# KhoaSoDienTu.net
KiCad netlist of a schematic drawn in Altium Designer
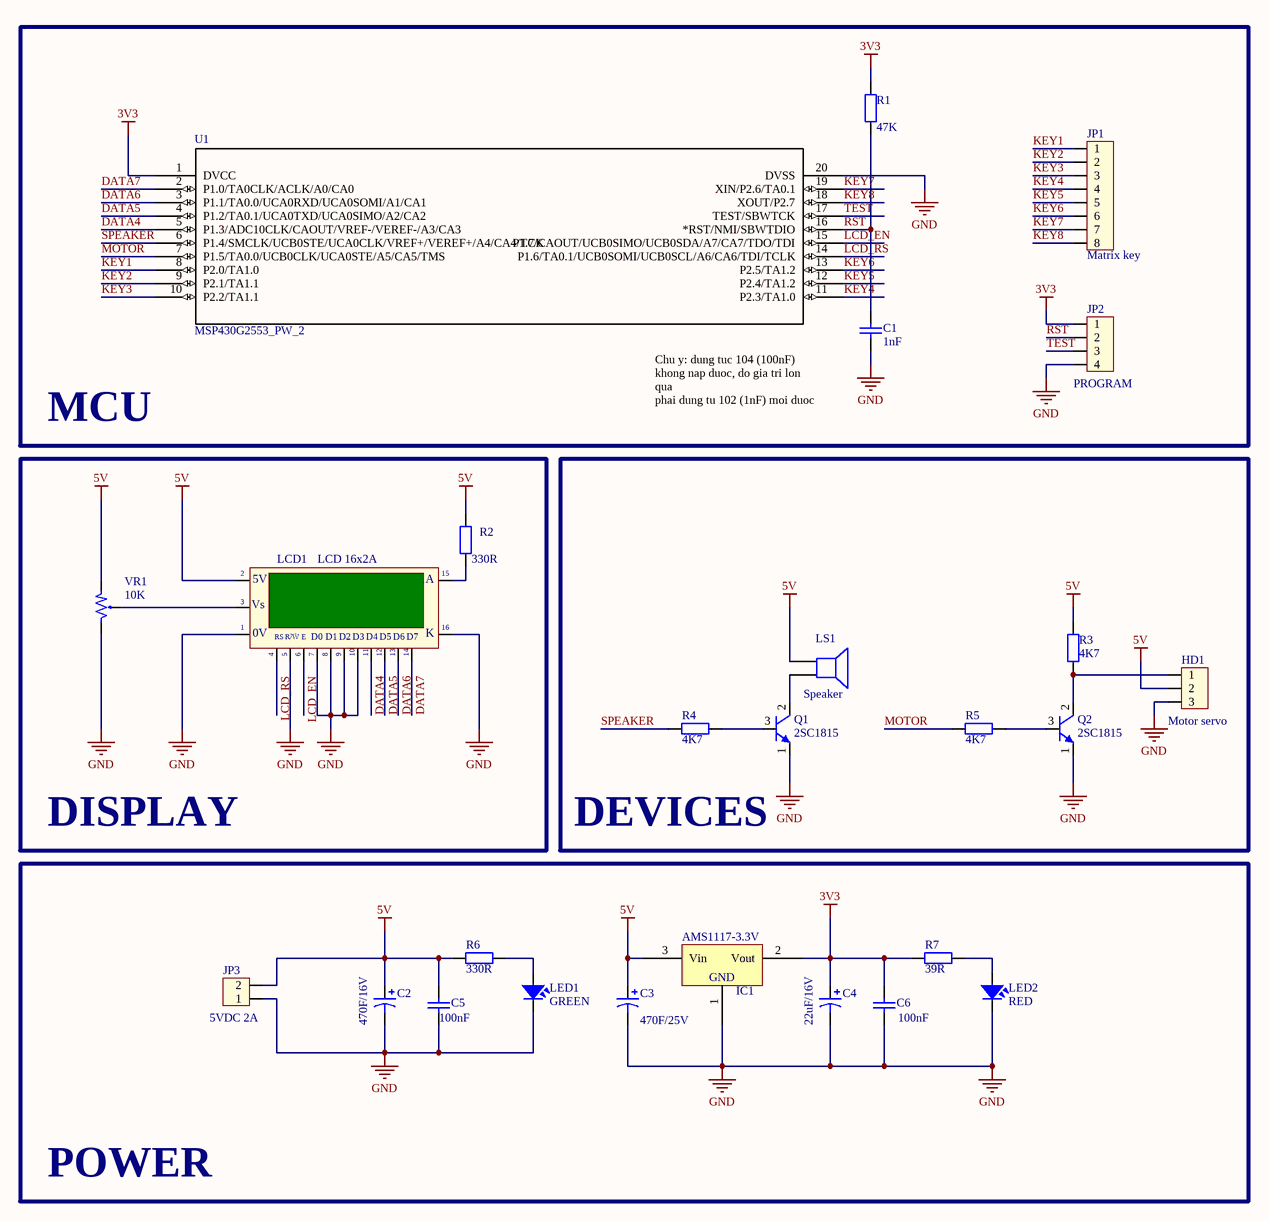
[diagram p0: KhoaSoDienTu.SchDoc]

(export (version "E")
  (design (tool "Eeschema 10.0.6"))
  (components
    (comp (ref "C1")
      (value "1nF")
      (footprint "Tu gom 104")
      (description "Capacitor")
      (fields (field (name "Comment") "Cap") (field (name "PUBLISHER") "Altium Limited"))
      (libsource (lib "Miscellaneous Devices") (part "Cap"))
    )
    (comp (ref "C2")
      (value "470F/16V")
      (footprint "CAP_470UF_16V")
      (description "Polarized Capacitor (Radial)")
      (fields (field (name "Comment") "Cap Pol1") (field (name "PUBLISHER") "Altium Limited"))
      (libsource (lib "Miscellaneous Devices") (part "Cap Pol1"))
    )
    (comp (ref "C3")
      (value "470F/25V")
      (footprint "CAP_470UF_25V")
      (description "Polarized Capacitor (Radial)")
      (fields (field (name "Comment") "Cap Pol1") (field (name "PUBLISHER") "Altium Limited"))
      (libsource (lib "Miscellaneous Devices") (part "Cap Pol1"))
    )
    (comp (ref "C4")
      (value "22uF/16V")
      (footprint "CAP_22UF_16V")
      (description "Polarized Capacitor (Radial)")
      (fields (field (name "Comment") "Cap Pol1") (field (name "PUBLISHER") "Altium Limited"))
      (libsource (lib "Miscellaneous Devices") (part "Cap Pol1"))
    )
    (comp (ref "C5")
      (value "100nF")
      (footprint "Tu gom 104")
      (description "Capacitor")
      (fields (field (name "Comment") "Cap") (field (name "PUBLISHER") "Altium Limited"))
      (libsource (lib "Miscellaneous Devices") (part "Cap"))
    )
    (comp (ref "C6")
      (value "100nF")
      (footprint "Tu gom 104")
      (description "Capacitor")
      (fields (field (name "Comment") "Cap") (field (name "PUBLISHER") "Altium Limited"))
      (libsource (lib "Miscellaneous Devices") (part "Cap"))
    )
    (comp (ref "HD1")
      (value "Motor servo")
      (footprint "Header_3")
      (description "Header 3 (Green)")
      (libsource (lib "lpson") (part "Hed3"))
    )
    (comp (ref "IC1")
      (value "AMS1117-3.3V")
      (footprint "AMS1117-3.3V")
      (libsource (lib "LuanVanPIR") (part "AMS1117"))
    )
    (comp (ref "JP1")
      (value "Matrix key")
      (footprint "Header_8")
      (description "Connector 8")
      (libsource (lib "lpson") (part "Con8"))
    )
    (comp (ref "JP2")
      (value "PROGRAM")
      (footprint "Header_4")
      (description "Connector 4")
      (libsource (lib "lpson") (part "Con4"))
    )
    (comp (ref "JP3")
      (value "5VDC 2A")
      (footprint "CON2")
      (description "Connector 2")
      (libsource (lib "lpson") (part "Con2"))
    )
    (comp (ref "LCD1")
      (value "LCD 16x2A")
      (footprint "LCD16x2")
      (description "LCD dipslay 16 char, 2 line")
      (libsource (lib "VNELEK") (part "LCD16x2A"))
    )
    (comp (ref "LED1")
      (value "GREEN")
      (footprint "LED3G")
      (description "LED Single colour Green and Red")
      (libsource (lib "VNELEK") (part "LED"))
    )
    (comp (ref "LED2")
      (value "RED")
      (footprint "LED3R")
      (description "LED Single colour Green and Red")
      (libsource (lib "VNELEK") (part "LED"))
    )
    (comp (ref "LS1")
      (value "Speaker")
      (footprint "SPEAKER")
      (description "Loudspeaker")
      (fields (field (name "PUBLISHER") "Altium Limited"))
      (libsource (lib "Miscellaneous Devices") (part "Speaker"))
    )
    (comp (ref "Q1")
      (value "2SC1815")
      (footprint "2SC1815")
      (description "Trans NPN 50V 150mA TO-92")
      (libsource (lib "lpson") (part "2SC1815"))
    )
    (comp (ref "Q2")
      (value "2SC1815")
      (footprint "2SC1815")
      (description "Trans NPN 50V 150mA TO-92")
      (libsource (lib "lpson") (part "2SC1815"))
    )
    (comp (ref "R1")
      (value "47K")
      (footprint "RES 1/4W CFR25")
      (description "Resistor")
      (fields (field (name "Comment") "Res2") (field (name "PUBLISHER") "Altium Limited"))
      (libsource (lib "Miscellaneous Devices") (part "Res2"))
    )
    (comp (ref "R2")
      (value "330R")
      (footprint "RES 1/4W CFR25")
      (description "Resistor")
      (fields (field (name "Comment") "Res2") (field (name "PUBLISHER") "Altium Limited"))
      (libsource (lib "Miscellaneous Devices") (part "Res2"))
    )
    (comp (ref "R3")
      (value "4K7")
      (footprint "RES 1/4W CFR25")
      (description "Resistor")
      (fields (field (name "Comment") "Res2") (field (name "PUBLISHER") "Altium Limited"))
      (libsource (lib "Miscellaneous Devices") (part "Res2"))
    )
    (comp (ref "R4")
      (value "4K7")
      (footprint "RES 1/4W CFR25")
      (description "Resistor")
      (fields (field (name "Comment") "Res2") (field (name "PUBLISHER") "Altium Limited"))
      (libsource (lib "") (part "Res2_2"))
    )
    (comp (ref "R5")
      (value "4K7")
      (footprint "RES 1/4W CFR25")
      (description "Resistor")
      (fields (field (name "Comment") "Res2") (field (name "PUBLISHER") "Altium Limited"))
      (libsource (lib "") (part "Res2_2"))
    )
    (comp (ref "R6")
      (value "330R")
      (footprint "RES 1/4W CFR25")
      (description "Resistor")
      (fields (field (name "Comment") "Res2") (field (name "PUBLISHER") "Altium Limited"))
      (libsource (lib "") (part "Res2_1"))
    )
    (comp (ref "R7")
      (value "39R")
      (footprint "RES 1/4W CFR25")
      (description "Resistor")
      (fields (field (name "Comment") "Res2") (field (name "PUBLISHER") "Altium Limited"))
      (libsource (lib "") (part "Res2_1"))
    )
    (comp (ref "U1")
      (value "MSP430G2553_PW_2")
      (footprint "MSP430G2553")
      (description "Imported")
      (fields
        (field (name "MANUFACTURER_PART_NUMBER") "msp430g2553_pw_20")
        (field (name "GENERIC_PART_NUMBER") "MSP430G2553")
      )
      (libsource (lib "MSP430G2553_PW_2") (part "MSP430G2553_PW_2"))
    )
    (comp (ref "VR1")
      (value "10K")
      (footprint "VR1")
      (description "Var Resistor")
      (libsource (lib "VNELEK") (part "VR1"))
    )
  )
  (nets
    (net (code "1") (name "/DATA4") (class "Default")
      (node (ref "LCD1") (pin "11") (pinfunction "D4_11") (pintype "passive"))
      (node (ref "U1") (pin "5") (pinfunction "P1.3/ADC10CLK/CAOUT/VREF-/VEREF-/A3/CA3_5") (pintype "bidirectional"))
    )
    (net (code "2") (name "/DATA5") (class "Default")
      (node (ref "LCD1") (pin "12") (pinfunction "D5_12") (pintype "passive"))
      (node (ref "U1") (pin "4") (pinfunction "P1.2/TA0.1/UCA0TXD/UCA0SIMO/A2/CA2_4") (pintype "bidirectional"))
    )
    (net (code "3") (name "/DATA6") (class "Default")
      (node (ref "LCD1") (pin "13") (pinfunction "D6_13") (pintype "passive"))
      (node (ref "U1") (pin "3") (pinfunction "P1.1/TA0.0/UCA0RXD/UCA0SOMI/A1/CA1_3") (pintype "bidirectional"))
    )
    (net (code "4") (name "/DATA7") (class "Default")
      (node (ref "LCD1") (pin "14") (pinfunction "D7_14") (pintype "passive"))
      (node (ref "U1") (pin "2") (pinfunction "P1.0/TA0CLK/ACLK/A0/CA0_2") (pintype "bidirectional"))
    )
    (net (code "5") (name "/KEY1") (class "Default")
      (node (ref "JP1") (pin "1") (pinfunction "1_1") (pintype "passive"))
      (node (ref "U1") (pin "8") (pinfunction "P2.0/TA1.0_8") (pintype "bidirectional"))
    )
    (net (code "6") (name "/KEY2") (class "Default")
      (node (ref "JP1") (pin "2") (pinfunction "2_2") (pintype "passive"))
      (node (ref "U1") (pin "9") (pinfunction "P2.1/TA1.1_9") (pintype "bidirectional"))
    )
    (net (code "7") (name "/KEY3") (class "Default")
      (node (ref "JP1") (pin "3") (pinfunction "3_3") (pintype "passive"))
      (node (ref "U1") (pin "10") (pinfunction "P2.2/TA1.1_10") (pintype "bidirectional"))
    )
    (net (code "8") (name "/KEY4") (class "Default")
      (node (ref "JP1") (pin "4") (pinfunction "4_4") (pintype "passive"))
      (node (ref "U1") (pin "11") (pinfunction "P2.3/TA1.0_11") (pintype "bidirectional"))
    )
    (net (code "9") (name "/KEY5") (class "Default")
      (node (ref "JP1") (pin "5") (pinfunction "5_5") (pintype "passive"))
      (node (ref "U1") (pin "12") (pinfunction "P2.4/TA1.2_12") (pintype "bidirectional"))
    )
    (net (code "10") (name "/KEY6") (class "Default")
      (node (ref "JP1") (pin "6") (pinfunction "6_6") (pintype "passive"))
      (node (ref "U1") (pin "13") (pinfunction "P2.5/TA1.2_13") (pintype "bidirectional"))
    )
    (net (code "11") (name "/KEY7") (class "Default")
      (node (ref "JP1") (pin "7") (pinfunction "7_7") (pintype "passive"))
      (node (ref "U1") (pin "19") (pinfunction "XIN/P2.6/TA0.1_19") (pintype "bidirectional"))
    )
    (net (code "12") (name "/KEY8") (class "Default")
      (node (ref "JP1") (pin "8") (pinfunction "8_8") (pintype "passive"))
      (node (ref "U1") (pin "18") (pinfunction "XOUT/P2.7_18") (pintype "bidirectional"))
    )
    (net (code "13") (name "/LCD_EN") (class "Default")
      (node (ref "LCD1") (pin "6") (pinfunction "~{EN}_6") (pintype "passive"))
      (node (ref "U1") (pin "15") (pinfunction "P1.7/CAOUT/UCB0SIMO/UCB0SDA/A7/CA7/TDO/TDI_15") (pintype "bidirectional"))
    )
    (net (code "14") (name "/LCD_RS") (class "Default")
      (node (ref "LCD1") (pin "4") (pinfunction "RS_4") (pintype "passive"))
      (node (ref "U1") (pin "14") (pinfunction "P1.6/TA0.1/UCB0SOMI/UCB0SCL/A6/CA6/TDI/TCLK_14") (pintype "bidirectional"))
    )
    (net (code "15") (name "/MOTOR") (class "Default")
      (node (ref "R5") (pin "1") (pinfunction "1_1") (pintype "passive"))
      (node (ref "U1") (pin "7") (pinfunction "P1.5/TA0.0/UCB0CLK/UCA0STE/A5/CA5/TMS_7") (pintype "bidirectional"))
    )
    (net (code "16") (name "/RST") (class "Default")
      (node (ref "C1") (pin "1") (pinfunction "1_1") (pintype "passive"))
      (node (ref "JP2") (pin "2") (pinfunction "2_2") (pintype "passive"))
      (node (ref "R1") (pin "1") (pinfunction "1_1") (pintype "passive"))
      (node (ref "U1") (pin "16") (pinfunction "*RST/NMI/SBWTDIO_16") (pintype "bidirectional"))
    )
    (net (code "17") (name "/SPEAKER") (class "Default")
      (node (ref "R4") (pin "1") (pinfunction "1_1") (pintype "passive"))
      (node (ref "U1") (pin "6") (pinfunction "P1.4/SMCLK/UCB0STE/UCA0CLK/VREF+/VEREF+/A4/CA4/TCK_6") (pintype "bidirectional"))
    )
    (net (code "18") (name "/TEST") (class "Default")
      (node (ref "JP2") (pin "3") (pinfunction "3_3") (pintype "passive"))
      (node (ref "U1") (pin "17") (pinfunction "TEST/SBWTCK_17") (pintype "bidirectional"))
    )
    (net (code "19") (name "3V3") (class "Default")
      (node (ref "C4") (pin "1") (pinfunction "1_1") (pintype "passive"))
      (node (ref "C6") (pin "2") (pinfunction "2_2") (pintype "passive"))
      (node (ref "IC1") (pin "2") (pinfunction "Vout_2") (pintype "passive"))
      (node (ref "JP2") (pin "1") (pinfunction "1_1") (pintype "passive"))
      (node (ref "R1") (pin "2") (pinfunction "2_2") (pintype "passive"))
      (node (ref "R7") (pin "2") (pinfunction "2_2") (pintype "passive"))
      (node (ref "U1") (pin "1") (pinfunction "DVCC_1") (pintype "power_in"))
    )
    (net (code "20") (name "5V") (class "Default")
      (node (ref "C2") (pin "1") (pinfunction "1_1") (pintype "passive"))
      (node (ref "C3") (pin "1") (pinfunction "1_1") (pintype "passive"))
      (node (ref "C5") (pin "2") (pinfunction "2_2") (pintype "passive"))
      (node (ref "HD1") (pin "2") (pinfunction "2_2") (pintype "passive"))
      (node (ref "IC1") (pin "3") (pinfunction "Vin_3") (pintype "passive"))
      (node (ref "JP3") (pin "2") (pinfunction "2_2") (pintype "passive"))
      (node (ref "LCD1") (pin "2") (pinfunction "VDD_2") (pintype "passive"))
      (node (ref "LS1") (pin "2") (pinfunction "2_2") (pintype "passive"))
      (node (ref "R2") (pin "2") (pinfunction "2_2") (pintype "passive"))
      (node (ref "R3") (pin "2") (pinfunction "2_2") (pintype "passive"))
      (node (ref "R6") (pin "2") (pinfunction "2_2") (pintype "passive"))
      (node (ref "VR1") (pin "1") (pinfunction "1_1") (pintype "passive"))
    )
    (net (code "21") (name "GND") (class "Default")
      (node (ref "C1") (pin "2") (pinfunction "2_2") (pintype "passive"))
      (node (ref "C2") (pin "2") (pinfunction "2_2") (pintype "passive"))
      (node (ref "C3") (pin "2") (pinfunction "2_2") (pintype "passive"))
      (node (ref "C4") (pin "2") (pinfunction "2_2") (pintype "passive"))
      (node (ref "C5") (pin "1") (pinfunction "1_1") (pintype "passive"))
      (node (ref "C6") (pin "1") (pinfunction "1_1") (pintype "passive"))
      (node (ref "HD1") (pin "3") (pinfunction "3_3") (pintype "passive"))
      (node (ref "IC1") (pin "1") (pinfunction "GND_1") (pintype "passive"))
      (node (ref "JP2") (pin "4") (pinfunction "4_4") (pintype "passive"))
      (node (ref "JP3") (pin "1") (pinfunction "1_1") (pintype "passive"))
      (node (ref "LCD1") (pin "1") (pinfunction "GND_1") (pintype "passive"))
      (node (ref "LCD1") (pin "10") (pinfunction "D3_10") (pintype "passive"))
      (node (ref "LCD1") (pin "16") (pinfunction "K_16") (pintype "passive"))
      (node (ref "LCD1") (pin "5") (pinfunction "R/~{W}_5") (pintype "passive"))
      (node (ref "LCD1") (pin "7") (pinfunction "D0_7") (pintype "passive"))
      (node (ref "LCD1") (pin "8") (pinfunction "D1_8") (pintype "passive"))
      (node (ref "LCD1") (pin "9") (pinfunction "D2_9") (pintype "passive"))
      (node (ref "LED1") (pin "2") (pinfunction "2_2") (pintype "passive"))
      (node (ref "LED2") (pin "2") (pinfunction "2_2") (pintype "passive"))
      (node (ref "Q1") (pin "1") (pinfunction "E_1") (pintype "passive"))
      (node (ref "Q2") (pin "1") (pinfunction "E_1") (pintype "passive"))
      (node (ref "U1") (pin "20") (pinfunction "DVSS_20") (pintype "power_in"))
      (node (ref "VR1") (pin "3") (pinfunction "3_3") (pintype "passive"))
    )
    (net (code "22") (name "Net-(LCD1-A)") (class "Default")
      (node (ref "LCD1") (pin "15") (pinfunction "A_15") (pintype "passive"))
      (node (ref "R2") (pin "1") (pinfunction "1_1") (pintype "passive"))
    )
    (net (code "23") (name "Net-(LCD1-VEE)") (class "Default")
      (node (ref "LCD1") (pin "3") (pinfunction "VEE_3") (pintype "passive"))
      (node (ref "VR1") (pin "2") (pinfunction "2_2") (pintype "passive"))
    )
    (net (code "24") (name "Net-(LED1-Pad1)") (class "Default")
      (node (ref "LED1") (pin "1") (pinfunction "1_1") (pintype "passive"))
      (node (ref "R6") (pin "1") (pinfunction "1_1") (pintype "passive"))
    )
    (net (code "25") (name "Net-(LED2-Pad1)") (class "Default")
      (node (ref "LED2") (pin "1") (pinfunction "1_1") (pintype "passive"))
      (node (ref "R7") (pin "1") (pinfunction "1_1") (pintype "passive"))
    )
    (net (code "26") (name "Net-(Q1-B)") (class "Default")
      (node (ref "Q1") (pin "3") (pinfunction "B_3") (pintype "passive"))
      (node (ref "R4") (pin "2") (pinfunction "2_2") (pintype "passive"))
    )
    (net (code "27") (name "Net-(Q1-C)") (class "Default")
      (node (ref "LS1") (pin "1") (pinfunction "1_1") (pintype "passive"))
      (node (ref "Q1") (pin "2") (pinfunction "C_2") (pintype "passive"))
    )
    (net (code "28") (name "Net-(Q2-B)") (class "Default")
      (node (ref "Q2") (pin "3") (pinfunction "B_3") (pintype "passive"))
      (node (ref "R5") (pin "2") (pinfunction "2_2") (pintype "passive"))
    )
    (net (code "29") (name "Net-(Q2-C)") (class "Default")
      (node (ref "HD1") (pin "1") (pinfunction "1_1") (pintype "passive"))
      (node (ref "Q2") (pin "2") (pinfunction "C_2") (pintype "passive"))
      (node (ref "R3") (pin "1") (pinfunction "1_1") (pintype "passive"))
    )
  )
)
